# turnRacingMainInput.net
KiCad netlist of a schematic drawn in Altium Designer
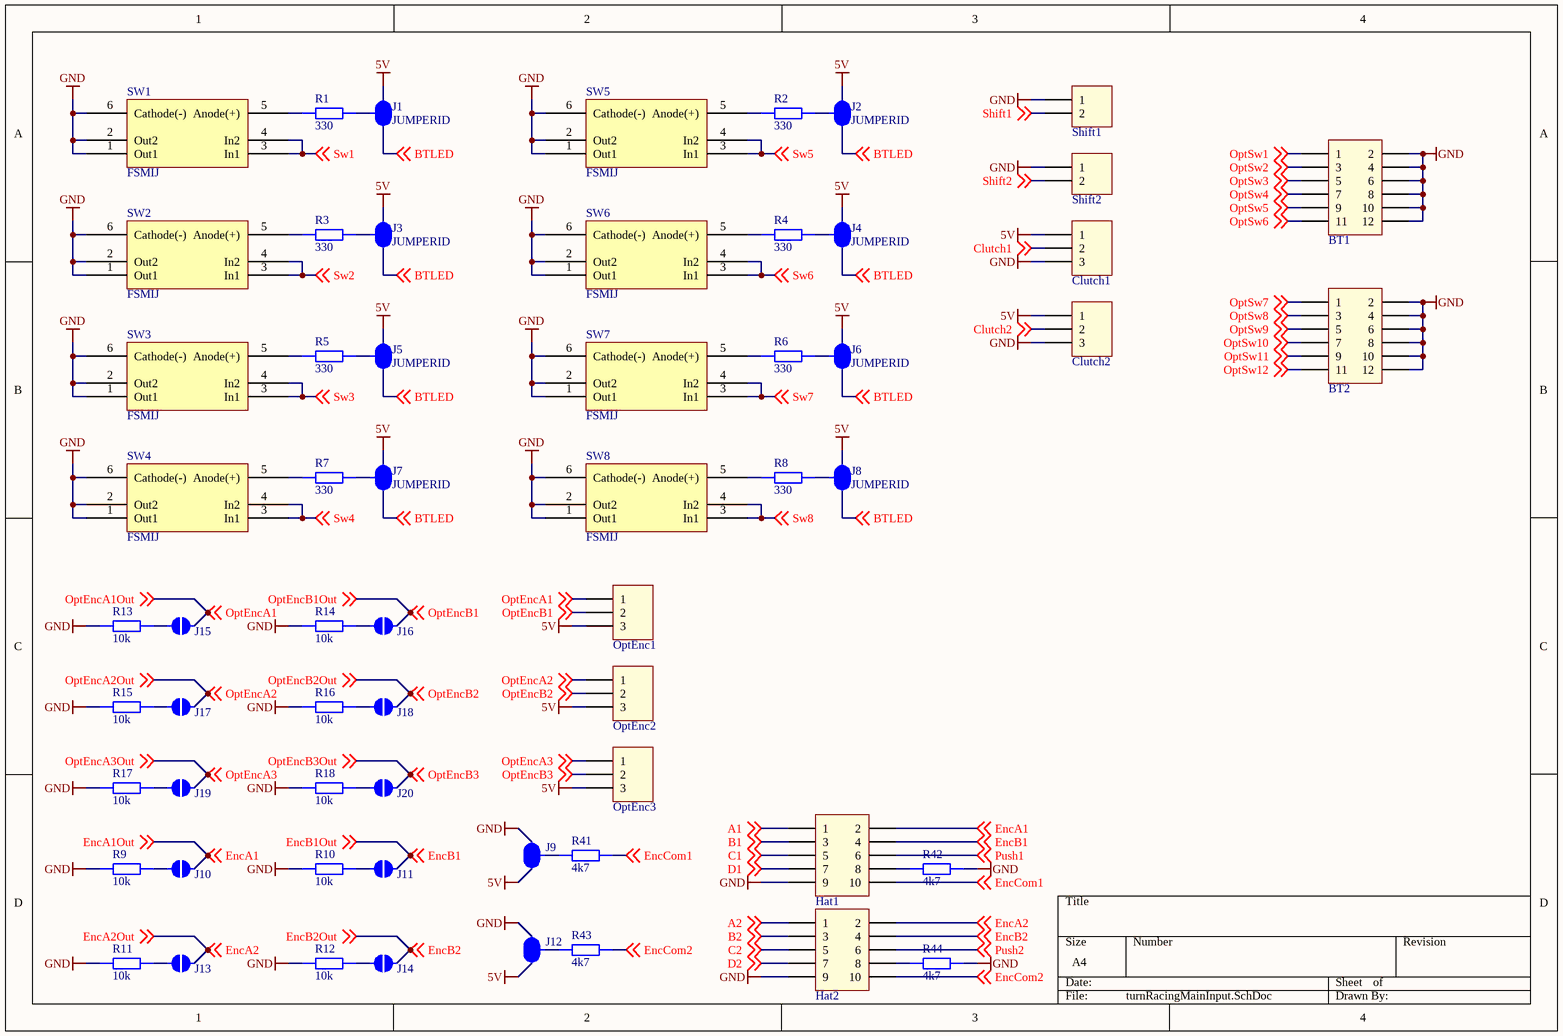
[diagram p0: turnRacingMainInput.SchDoc]

(export (version "E")
  (design (tool "Eeschema 10.0.6"))
  (components
    (comp (ref "BT1")
      (value "61301221121")
      (footprint "61301221121")
      (description "WR-PHD 2.54 mm THT Dual Pin Header, 12p")
      (fields (field (name "PUBLISHER") "Wurth Elektronik"))
      (libsource (lib "ALTIUM-PHD_2_54_THT_DUAL_PIN_HEADER_6130XX21121") (part "61301221121"))
    )
    (comp (ref "BT2")
      (value "61301221121")
      (footprint "61301221121")
      (description "WR-PHD 2.54 mm THT Dual Pin Header, 12p")
      (fields (field (name "PUBLISHER") "Wurth Elektronik"))
      (libsource (lib "ALTIUM-PHD_2_54_THT_DUAL_PIN_HEADER_6130XX21121") (part "61301221121"))
    )
    (comp (ref "Clutch1")
      (value "61300311121")
      (footprint "61300311121")
      (description "WR-PHD 2.54 mm THT Pin Header, 3p")
      (fields (field (name "PUBLISHER") "Wurth Elektronik"))
      (libsource (lib "ALTIUM-PHD_2_54_THT_DUAL_PIN_HEADER_6130XX21121") (part "61300311121"))
    )
    (comp (ref "Clutch2")
      (value "61300311121")
      (footprint "61300311121")
      (description "WR-PHD 2.54 mm THT Pin Header, 3p")
      (fields (field (name "PUBLISHER") "Wurth Elektronik"))
      (libsource (lib "ALTIUM-PHD_2_54_THT_DUAL_PIN_HEADER_6130XX21121") (part "61300311121"))
    )
    (comp (ref "Hat1")
      (value "61301021121")
      (footprint "61301021121")
      (description "WR-PHD 2.54 mm THT Dual Pin Header, 10p")
      (fields (field (name "PUBLISHER") "Wurth Elektronik"))
      (libsource (lib "ALTIUM-PHD_2_54_THT_DUAL_PIN_HEADER_6130XX21121") (part "61301021121"))
    )
    (comp (ref "Hat2")
      (value "61301021121")
      (footprint "61301021121")
      (description "WR-PHD 2.54 mm THT Dual Pin Header, 10p")
      (fields (field (name "PUBLISHER") "Wurth Elektronik"))
      (libsource (lib "ALTIUM-PHD_2_54_THT_DUAL_PIN_HEADER_6130XX21121") (part "61301021121"))
    )
    (comp (ref "J1")
      (value "JUMPERID")
      (footprint "SMD-JUMPER-3")
      (libsource (lib "Standardbauteile") (part "SMD Jumper 3"))
    )
    (comp (ref "J2")
      (value "JUMPERID")
      (footprint "SMD-JUMPER-3")
      (libsource (lib "Standardbauteile") (part "SMD Jumper 3"))
    )
    (comp (ref "J3")
      (value "JUMPERID")
      (footprint "SMD-JUMPER-3")
      (libsource (lib "Standardbauteile") (part "SMD Jumper 3"))
    )
    (comp (ref "J4")
      (value "JUMPERID")
      (footprint "SMD-JUMPER-3")
      (libsource (lib "Standardbauteile") (part "SMD Jumper 3"))
    )
    (comp (ref "J5")
      (value "JUMPERID")
      (footprint "SMD-JUMPER-3")
      (libsource (lib "Standardbauteile") (part "SMD Jumper 3"))
    )
    (comp (ref "J6")
      (value "JUMPERID")
      (footprint "SMD-JUMPER-3")
      (libsource (lib "Standardbauteile") (part "SMD Jumper 3"))
    )
    (comp (ref "J7")
      (value "JUMPERID")
      (footprint "SMD-JUMPER-3")
      (libsource (lib "Standardbauteile") (part "SMD Jumper 3"))
    )
    (comp (ref "J8")
      (value "JUMPERID")
      (footprint "SMD-JUMPER-3")
      (libsource (lib "Standardbauteile") (part "SMD Jumper 3"))
    )
    (comp (ref "J9")
      (value "JUMPERID")
      (footprint "SMD-JUMPER-3")
      (libsource (lib "") (part "SMD Jumper 3_1"))
    )
    (comp (ref "J10")
      (value "SMD Jumper open")
      (footprint "SMD-JUMPER-OPEN")
      (libsource (lib "Standardbauteile") (part "SMD Jumper open"))
    )
    (comp (ref "J11")
      (value "SMD Jumper open")
      (footprint "SMD-JUMPER-OPEN")
      (libsource (lib "Standardbauteile") (part "SMD Jumper open"))
    )
    (comp (ref "J12")
      (value "JUMPERID")
      (footprint "SMD-JUMPER-3")
      (libsource (lib "") (part "SMD Jumper 3_1"))
    )
    (comp (ref "J13")
      (value "SMD Jumper open")
      (footprint "SMD-JUMPER-OPEN")
      (libsource (lib "Standardbauteile") (part "SMD Jumper open"))
    )
    (comp (ref "J14")
      (value "SMD Jumper open")
      (footprint "SMD-JUMPER-OPEN")
      (libsource (lib "Standardbauteile") (part "SMD Jumper open"))
    )
    (comp (ref "J15")
      (value "SMD Jumper open")
      (footprint "SMD-JUMPER-OPEN")
      (libsource (lib "Standardbauteile") (part "SMD Jumper open"))
    )
    (comp (ref "J16")
      (value "SMD Jumper open")
      (footprint "SMD-JUMPER-OPEN")
      (libsource (lib "Standardbauteile") (part "SMD Jumper open"))
    )
    (comp (ref "J17")
      (value "SMD Jumper open")
      (footprint "SMD-JUMPER-OPEN")
      (libsource (lib "Standardbauteile") (part "SMD Jumper open"))
    )
    (comp (ref "J18")
      (value "SMD Jumper open")
      (footprint "SMD-JUMPER-OPEN")
      (libsource (lib "Standardbauteile") (part "SMD Jumper open"))
    )
    (comp (ref "J19")
      (value "SMD Jumper open")
      (footprint "SMD-JUMPER-OPEN")
      (libsource (lib "Standardbauteile") (part "SMD Jumper open"))
    )
    (comp (ref "J20")
      (value "SMD Jumper open")
      (footprint "SMD-JUMPER-OPEN")
      (libsource (lib "Standardbauteile") (part "SMD Jumper open"))
    )
    (comp (ref "OptEnc1")
      (value "61300311121")
      (footprint "61300311121")
      (description "WR-PHD 2.54 mm THT Pin Header, 3p")
      (fields (field (name "PUBLISHER") "Wurth Elektronik"))
      (libsource (lib "ALTIUM-PHD_2_54_THT_DUAL_PIN_HEADER_6130XX21121") (part "61300311121"))
    )
    (comp (ref "OptEnc2")
      (value "61300311121")
      (footprint "61300311121")
      (description "WR-PHD 2.54 mm THT Pin Header, 3p")
      (fields (field (name "PUBLISHER") "Wurth Elektronik"))
      (libsource (lib "ALTIUM-PHD_2_54_THT_DUAL_PIN_HEADER_6130XX21121") (part "61300311121"))
    )
    (comp (ref "OptEnc3")
      (value "61300311121")
      (footprint "61300311121")
      (description "WR-PHD 2.54 mm THT Pin Header, 3p")
      (fields (field (name "PUBLISHER") "Wurth Elektronik"))
      (libsource (lib "ALTIUM-PHD_2_54_THT_DUAL_PIN_HEADER_6130XX21121") (part "61300311121"))
    )
    (comp (ref "R1")
      (value "330")
      (footprint "STACKPOLE CSR0603")
      (description "Resistor with multiple footprints")
      (fields (field (name "Comment") "SMD Resistor"))
      (libsource (lib "") (part "SMD Resistor_1"))
    )
    (comp (ref "R2")
      (value "330")
      (footprint "STACKPOLE CSR0603")
      (description "Resistor with multiple footprints")
      (fields (field (name "Comment") "SMD Resistor"))
      (libsource (lib "") (part "SMD Resistor_1"))
    )
    (comp (ref "R3")
      (value "330")
      (footprint "STACKPOLE CSR0603")
      (description "Resistor with multiple footprints")
      (fields (field (name "Comment") "SMD Resistor"))
      (libsource (lib "") (part "SMD Resistor_1"))
    )
    (comp (ref "R4")
      (value "330")
      (footprint "STACKPOLE CSR0603")
      (description "Resistor with multiple footprints")
      (fields (field (name "Comment") "SMD Resistor"))
      (libsource (lib "") (part "SMD Resistor_1"))
    )
    (comp (ref "R5")
      (value "330")
      (footprint "STACKPOLE CSR0603")
      (description "Resistor with multiple footprints")
      (fields (field (name "Comment") "SMD Resistor"))
      (libsource (lib "") (part "SMD Resistor_1"))
    )
    (comp (ref "R6")
      (value "330")
      (footprint "STACKPOLE CSR0603")
      (description "Resistor with multiple footprints")
      (fields (field (name "Comment") "SMD Resistor"))
      (libsource (lib "") (part "SMD Resistor_1"))
    )
    (comp (ref "R7")
      (value "330")
      (footprint "STACKPOLE CSR0603")
      (description "Resistor with multiple footprints")
      (fields (field (name "Comment") "SMD Resistor"))
      (libsource (lib "") (part "SMD Resistor_1"))
    )
    (comp (ref "R8")
      (value "330")
      (footprint "STACKPOLE CSR0603")
      (description "Resistor with multiple footprints")
      (fields (field (name "Comment") "SMD Resistor"))
      (libsource (lib "") (part "SMD Resistor_1"))
    )
    (comp (ref "R9")
      (value "10k")
      (footprint "STACKPOLE CSR0603")
      (description "Resistor with multiple footprints")
      (fields (field (name "Comment") "SMD Resistor"))
      (libsource (lib "") (part "SMD Resistor_1"))
    )
    (comp (ref "R10")
      (value "10k")
      (footprint "STACKPOLE CSR0603")
      (description "Resistor with multiple footprints")
      (fields (field (name "Comment") "SMD Resistor"))
      (libsource (lib "") (part "SMD Resistor_1"))
    )
    (comp (ref "R11")
      (value "10k")
      (footprint "STACKPOLE CSR0603")
      (description "Resistor with multiple footprints")
      (fields (field (name "Comment") "SMD Resistor"))
      (libsource (lib "") (part "SMD Resistor_1"))
    )
    (comp (ref "R12")
      (value "10k")
      (footprint "STACKPOLE CSR0603")
      (description "Resistor with multiple footprints")
      (fields (field (name "Comment") "SMD Resistor"))
      (libsource (lib "") (part "SMD Resistor_1"))
    )
    (comp (ref "R13")
      (value "10k")
      (footprint "STACKPOLE CSR0603")
      (description "Resistor with multiple footprints")
      (fields (field (name "Comment") "SMD Resistor"))
      (libsource (lib "") (part "SMD Resistor_1"))
    )
    (comp (ref "R14")
      (value "10k")
      (footprint "STACKPOLE CSR0603")
      (description "Resistor with multiple footprints")
      (fields (field (name "Comment") "SMD Resistor"))
      (libsource (lib "") (part "SMD Resistor_1"))
    )
    (comp (ref "R15")
      (value "10k")
      (footprint "STACKPOLE CSR0603")
      (description "Resistor with multiple footprints")
      (fields (field (name "Comment") "SMD Resistor"))
      (libsource (lib "") (part "SMD Resistor_1"))
    )
    (comp (ref "R16")
      (value "10k")
      (footprint "STACKPOLE CSR0603")
      (description "Resistor with multiple footprints")
      (fields (field (name "Comment") "SMD Resistor"))
      (libsource (lib "") (part "SMD Resistor_1"))
    )
    (comp (ref "R17")
      (value "10k")
      (footprint "STACKPOLE CSR0603")
      (description "Resistor with multiple footprints")
      (fields (field (name "Comment") "SMD Resistor"))
      (libsource (lib "") (part "SMD Resistor_1"))
    )
    (comp (ref "R18")
      (value "10k")
      (footprint "STACKPOLE CSR0603")
      (description "Resistor with multiple footprints")
      (fields (field (name "Comment") "SMD Resistor"))
      (libsource (lib "") (part "SMD Resistor_1"))
    )
    (comp (ref "R41")
      (value "4k7")
      (footprint "STACKPOLE CSR0603")
      (description "Resistor with multiple footprints")
      (fields (field (name "Comment") "SMD Resistor"))
      (libsource (lib "Standardbauteile") (part "SMD Resistor"))
    )
    (comp (ref "R42")
      (value "4k7")
      (footprint "STACKPOLE CSR0603")
      (description "Resistor with multiple footprints")
      (fields (field (name "Comment") "SMD Resistor"))
      (libsource (lib "Standardbauteile") (part "SMD Resistor"))
    )
    (comp (ref "R43")
      (value "4k7")
      (footprint "STACKPOLE CSR0603")
      (description "Resistor with multiple footprints")
      (fields (field (name "Comment") "SMD Resistor"))
      (libsource (lib "Standardbauteile") (part "SMD Resistor"))
    )
    (comp (ref "R44")
      (value "4k7")
      (footprint "STACKPOLE CSR0603")
      (description "Resistor with multiple footprints")
      (fields (field (name "Comment") "SMD Resistor"))
      (libsource (lib "Standardbauteile") (part "SMD Resistor"))
    )
    (comp (ref "Shift1")
      (value "61300211121")
      (footprint "61300211121")
      (description "WR-PHD 2.54 mm THT Pin Header, 2p")
      (fields (field (name "PUBLISHER") "Wurth Elektronik"))
      (libsource (lib "ALTIUM-PHD_2_54_THT_DUAL_PIN_HEADER_6130XX21121") (part "61300211121"))
    )
    (comp (ref "Shift2")
      (value "61300211121")
      (footprint "61300211121")
      (description "WR-PHD 2.54 mm THT Pin Header, 2p")
      (fields (field (name "PUBLISHER") "Wurth Elektronik"))
      (libsource (lib "ALTIUM-PHD_2_54_THT_DUAL_PIN_HEADER_6130XX21121") (part "61300211121"))
    )
    (comp (ref "SW1") (value "FSMIJ") (footprint "FSMIJ") (libsource (lib "Eric") (part "FSMIJ")))
    (comp (ref "SW2") (value "FSMIJ") (footprint "FSMIJ") (libsource (lib "Eric") (part "FSMIJ")))
    (comp (ref "SW3") (value "FSMIJ") (footprint "FSMIJ") (libsource (lib "Eric") (part "FSMIJ")))
    (comp (ref "SW4") (value "FSMIJ") (footprint "FSMIJ") (libsource (lib "Eric") (part "FSMIJ")))
    (comp (ref "SW5") (value "FSMIJ") (footprint "FSMIJ") (libsource (lib "Eric") (part "FSMIJ")))
    (comp (ref "SW6") (value "FSMIJ") (footprint "FSMIJ") (libsource (lib "Eric") (part "FSMIJ")))
    (comp (ref "SW7") (value "FSMIJ") (footprint "FSMIJ") (libsource (lib "Eric") (part "FSMIJ")))
    (comp (ref "SW8") (value "FSMIJ") (footprint "FSMIJ") (libsource (lib "Eric") (part "FSMIJ")))
  )
  (nets
    (net (code "1") (name "5V") (class "Default")
      (node (ref "Clutch1") (pin "1") (pinfunction "1_1") (pintype "passive"))
      (node (ref "Clutch2") (pin "1") (pinfunction "1_1") (pintype "passive"))
      (node (ref "J1") (pin "3") (pinfunction "3_3") (pintype "passive"))
      (node (ref "J12") (pin "3") (pinfunction "3_3") (pintype "passive"))
      (node (ref "J2") (pin "3") (pinfunction "3_3") (pintype "passive"))
      (node (ref "J3") (pin "3") (pinfunction "3_3") (pintype "passive"))
      (node (ref "J4") (pin "3") (pinfunction "3_3") (pintype "passive"))
      (node (ref "J5") (pin "3") (pinfunction "3_3") (pintype "passive"))
      (node (ref "J6") (pin "3") (pinfunction "3_3") (pintype "passive"))
      (node (ref "J7") (pin "3") (pinfunction "3_3") (pintype "passive"))
      (node (ref "J8") (pin "3") (pinfunction "3_3") (pintype "passive"))
      (node (ref "J9") (pin "3") (pinfunction "3_3") (pintype "passive"))
      (node (ref "OptEnc1") (pin "3") (pinfunction "3_3") (pintype "passive"))
      (node (ref "OptEnc2") (pin "3") (pinfunction "3_3") (pintype "passive"))
      (node (ref "OptEnc3") (pin "3") (pinfunction "3_3") (pintype "passive"))
    )
    (net (code "2") (name "A1") (class "Default")
      (node (ref "Hat1") (pin "1") (pinfunction "1_1") (pintype "passive"))
    )
    (net (code "3") (name "A2") (class "Default")
      (node (ref "Hat2") (pin "1") (pinfunction "1_1") (pintype "passive"))
    )
    (net (code "4") (name "B1") (class "Default")
      (node (ref "Hat1") (pin "3") (pinfunction "3_3") (pintype "passive"))
    )
    (net (code "5") (name "B2") (class "Default")
      (node (ref "Hat2") (pin "3") (pinfunction "3_3") (pintype "passive"))
    )
    (net (code "6") (name "BTLED") (class "Default")
      (node (ref "J1") (pin "1") (pinfunction "1_1") (pintype "passive"))
      (node (ref "J2") (pin "1") (pinfunction "1_1") (pintype "passive"))
      (node (ref "J3") (pin "1") (pinfunction "1_1") (pintype "passive"))
      (node (ref "J4") (pin "1") (pinfunction "1_1") (pintype "passive"))
      (node (ref "J5") (pin "1") (pinfunction "1_1") (pintype "passive"))
      (node (ref "J6") (pin "1") (pinfunction "1_1") (pintype "passive"))
      (node (ref "J7") (pin "1") (pinfunction "1_1") (pintype "passive"))
      (node (ref "J8") (pin "1") (pinfunction "1_1") (pintype "passive"))
    )
    (net (code "7") (name "C1") (class "Default")
      (node (ref "Hat1") (pin "5") (pinfunction "5_5") (pintype "passive"))
    )
    (net (code "8") (name "C2") (class "Default")
      (node (ref "Hat2") (pin "5") (pinfunction "5_5") (pintype "passive"))
    )
    (net (code "9") (name "Clutch1") (class "Default")
      (node (ref "Clutch1") (pin "2") (pinfunction "2_2") (pintype "passive"))
    )
    (net (code "10") (name "Clutch2") (class "Default")
      (node (ref "Clutch2") (pin "2") (pinfunction "2_2") (pintype "passive"))
    )
    (net (code "11") (name "D1") (class "Default")
      (node (ref "Hat1") (pin "7") (pinfunction "7_7") (pintype "passive"))
    )
    (net (code "12") (name "D2") (class "Default")
      (node (ref "Hat2") (pin "7") (pinfunction "7_7") (pintype "passive"))
    )
    (net (code "13") (name "EncA1") (class "Default")
      (node (ref "Hat1") (pin "2") (pinfunction "2_2") (pintype "passive"))
      (node (ref "J10") (pin "1") (pinfunction "1_1") (pintype "passive"))
    )
    (net (code "14") (name "EncA2") (class "Default")
      (node (ref "Hat2") (pin "2") (pinfunction "2_2") (pintype "passive"))
      (node (ref "J13") (pin "1") (pinfunction "1_1") (pintype "passive"))
    )
    (net (code "15") (name "EncB1") (class "Default")
      (node (ref "Hat1") (pin "4") (pinfunction "4_4") (pintype "passive"))
      (node (ref "J11") (pin "1") (pinfunction "1_1") (pintype "passive"))
    )
    (net (code "16") (name "EncB2") (class "Default")
      (node (ref "Hat2") (pin "4") (pinfunction "4_4") (pintype "passive"))
      (node (ref "J14") (pin "1") (pinfunction "1_1") (pintype "passive"))
    )
    (net (code "17") (name "EncCom1") (class "Default")
      (node (ref "Hat1") (pin "10") (pinfunction "10_10") (pintype "passive"))
      (node (ref "R41") (pin "1") (pinfunction "1_1") (pintype "passive"))
    )
    (net (code "18") (name "EncCom2") (class "Default")
      (node (ref "Hat2") (pin "10") (pinfunction "10_10") (pintype "passive"))
      (node (ref "R43") (pin "1") (pinfunction "1_1") (pintype "passive"))
    )
    (net (code "19") (name "GND") (class "Default")
      (node (ref "BT1") (pin "10") (pinfunction "10_10") (pintype "passive"))
      (node (ref "BT1") (pin "12") (pinfunction "12_12") (pintype "passive"))
      (node (ref "BT1") (pin "2") (pinfunction "2_2") (pintype "passive"))
      (node (ref "BT1") (pin "4") (pinfunction "4_4") (pintype "passive"))
      (node (ref "BT1") (pin "6") (pinfunction "6_6") (pintype "passive"))
      (node (ref "BT1") (pin "8") (pinfunction "8_8") (pintype "passive"))
      (node (ref "BT2") (pin "10") (pinfunction "10_10") (pintype "passive"))
      (node (ref "BT2") (pin "12") (pinfunction "12_12") (pintype "passive"))
      (node (ref "BT2") (pin "2") (pinfunction "2_2") (pintype "passive"))
      (node (ref "BT2") (pin "4") (pinfunction "4_4") (pintype "passive"))
      (node (ref "BT2") (pin "6") (pinfunction "6_6") (pintype "passive"))
      (node (ref "BT2") (pin "8") (pinfunction "8_8") (pintype "passive"))
      (node (ref "Clutch1") (pin "3") (pinfunction "3_3") (pintype "passive"))
      (node (ref "Clutch2") (pin "3") (pinfunction "3_3") (pintype "passive"))
      (node (ref "Hat1") (pin "9") (pinfunction "9_9") (pintype "passive"))
      (node (ref "Hat2") (pin "9") (pinfunction "9_9") (pintype "passive"))
      (node (ref "J12") (pin "1") (pinfunction "1_1") (pintype "passive"))
      (node (ref "J9") (pin "1") (pinfunction "1_1") (pintype "passive"))
      (node (ref "R10") (pin "2") (pinfunction "2_2") (pintype "passive"))
      (node (ref "R11") (pin "2") (pinfunction "2_2") (pintype "passive"))
      (node (ref "R12") (pin "2") (pinfunction "2_2") (pintype "passive"))
      (node (ref "R13") (pin "2") (pinfunction "2_2") (pintype "passive"))
      (node (ref "R14") (pin "2") (pinfunction "2_2") (pintype "passive"))
      (node (ref "R15") (pin "2") (pinfunction "2_2") (pintype "passive"))
      (node (ref "R16") (pin "2") (pinfunction "2_2") (pintype "passive"))
      (node (ref "R17") (pin "2") (pinfunction "2_2") (pintype "passive"))
      (node (ref "R18") (pin "2") (pinfunction "2_2") (pintype "passive"))
      (node (ref "R42") (pin "1") (pinfunction "1_1") (pintype "passive"))
      (node (ref "R44") (pin "1") (pinfunction "1_1") (pintype "passive"))
      (node (ref "R9") (pin "2") (pinfunction "2_2") (pintype "passive"))
      (node (ref "SW1") (pin "1") (pinfunction "Out1_1") (pintype "passive"))
      (node (ref "SW1") (pin "2") (pinfunction "Out2_2") (pintype "passive"))
      (node (ref "SW1") (pin "6") (pinfunction "Cathode(-)_6") (pintype "passive"))
      (node (ref "SW2") (pin "1") (pinfunction "Out1_1") (pintype "passive"))
      (node (ref "SW2") (pin "2") (pinfunction "Out2_2") (pintype "passive"))
      (node (ref "SW2") (pin "6") (pinfunction "Cathode(-)_6") (pintype "passive"))
      (node (ref "SW3") (pin "1") (pinfunction "Out1_1") (pintype "passive"))
      (node (ref "SW3") (pin "2") (pinfunction "Out2_2") (pintype "passive"))
      (node (ref "SW3") (pin "6") (pinfunction "Cathode(-)_6") (pintype "passive"))
      (node (ref "SW4") (pin "1") (pinfunction "Out1_1") (pintype "passive"))
      (node (ref "SW4") (pin "2") (pinfunction "Out2_2") (pintype "passive"))
      (node (ref "SW4") (pin "6") (pinfunction "Cathode(-)_6") (pintype "passive"))
      (node (ref "SW5") (pin "1") (pinfunction "Out1_1") (pintype "passive"))
      (node (ref "SW5") (pin "2") (pinfunction "Out2_2") (pintype "passive"))
      (node (ref "SW5") (pin "6") (pinfunction "Cathode(-)_6") (pintype "passive"))
      (node (ref "SW6") (pin "1") (pinfunction "Out1_1") (pintype "passive"))
      (node (ref "SW6") (pin "2") (pinfunction "Out2_2") (pintype "passive"))
      (node (ref "SW6") (pin "6") (pinfunction "Cathode(-)_6") (pintype "passive"))
      (node (ref "SW7") (pin "1") (pinfunction "Out1_1") (pintype "passive"))
      (node (ref "SW7") (pin "2") (pinfunction "Out2_2") (pintype "passive"))
      (node (ref "SW7") (pin "6") (pinfunction "Cathode(-)_6") (pintype "passive"))
      (node (ref "SW8") (pin "1") (pinfunction "Out1_1") (pintype "passive"))
      (node (ref "SW8") (pin "2") (pinfunction "Out2_2") (pintype "passive"))
      (node (ref "SW8") (pin "6") (pinfunction "Cathode(-)_6") (pintype "passive"))
      (node (ref "Shift1") (pin "1") (pinfunction "1_1") (pintype "passive"))
      (node (ref "Shift2") (pin "1") (pinfunction "1_1") (pintype "passive"))
    )
    (net (code "20") (name "Net-(Hat1-Pad8)") (class "Default")
      (node (ref "Hat1") (pin "8") (pinfunction "8_8") (pintype "passive"))
      (node (ref "R42") (pin "2") (pinfunction "2_2") (pintype "passive"))
    )
    (net (code "21") (name "Net-(Hat2-Pad8)") (class "Default")
      (node (ref "Hat2") (pin "8") (pinfunction "8_8") (pintype "passive"))
      (node (ref "R44") (pin "2") (pinfunction "2_2") (pintype "passive"))
    )
    (net (code "22") (name "Net-(J1-Pad2)") (class "Default")
      (node (ref "J1") (pin "2") (pinfunction "2_2") (pintype "passive"))
      (node (ref "R1") (pin "1") (pinfunction "1_1") (pintype "passive"))
    )
    (net (code "23") (name "Net-(J2-Pad2)") (class "Default")
      (node (ref "J2") (pin "2") (pinfunction "2_2") (pintype "passive"))
      (node (ref "R2") (pin "1") (pinfunction "1_1") (pintype "passive"))
    )
    (net (code "24") (name "Net-(J3-Pad2)") (class "Default")
      (node (ref "J3") (pin "2") (pinfunction "2_2") (pintype "passive"))
      (node (ref "R3") (pin "1") (pinfunction "1_1") (pintype "passive"))
    )
    (net (code "25") (name "Net-(J4-Pad2)") (class "Default")
      (node (ref "J4") (pin "2") (pinfunction "2_2") (pintype "passive"))
      (node (ref "R4") (pin "1") (pinfunction "1_1") (pintype "passive"))
    )
    (net (code "26") (name "Net-(J5-Pad2)") (class "Default")
      (node (ref "J5") (pin "2") (pinfunction "2_2") (pintype "passive"))
      (node (ref "R5") (pin "1") (pinfunction "1_1") (pintype "passive"))
    )
    (net (code "27") (name "Net-(J6-Pad2)") (class "Default")
      (node (ref "J6") (pin "2") (pinfunction "2_2") (pintype "passive"))
      (node (ref "R6") (pin "1") (pinfunction "1_1") (pintype "passive"))
    )
    (net (code "28") (name "Net-(J7-Pad2)") (class "Default")
      (node (ref "J7") (pin "2") (pinfunction "2_2") (pintype "passive"))
      (node (ref "R7") (pin "1") (pinfunction "1_1") (pintype "passive"))
    )
    (net (code "29") (name "Net-(J8-Pad2)") (class "Default")
      (node (ref "J8") (pin "2") (pinfunction "2_2") (pintype "passive"))
      (node (ref "R8") (pin "1") (pinfunction "1_1") (pintype "passive"))
    )
    (net (code "30") (name "Net-(J9-Pad2)") (class "Default")
      (node (ref "J9") (pin "2") (pinfunction "2_2") (pintype "passive"))
      (node (ref "R41") (pin "2") (pinfunction "2_2") (pintype "passive"))
    )
    (net (code "31") (name "Net-(J10-Pad2)") (class "Default")
      (node (ref "J10") (pin "2") (pinfunction "2_2") (pintype "passive"))
      (node (ref "R9") (pin "1") (pinfunction "1_1") (pintype "passive"))
    )
    (net (code "32") (name "Net-(J11-Pad2)") (class "Default")
      (node (ref "J11") (pin "2") (pinfunction "2_2") (pintype "passive"))
      (node (ref "R10") (pin "1") (pinfunction "1_1") (pintype "passive"))
    )
    (net (code "33") (name "Net-(J12-Pad2)") (class "Default")
      (node (ref "J12") (pin "2") (pinfunction "2_2") (pintype "passive"))
      (node (ref "R43") (pin "2") (pinfunction "2_2") (pintype "passive"))
    )
    (net (code "34") (name "Net-(J13-Pad2)") (class "Default")
      (node (ref "J13") (pin "2") (pinfunction "2_2") (pintype "passive"))
      (node (ref "R11") (pin "1") (pinfunction "1_1") (pintype "passive"))
    )
    (net (code "35") (name "Net-(J14-Pad2)") (class "Default")
      (node (ref "J14") (pin "2") (pinfunction "2_2") (pintype "passive"))
      (node (ref "R12") (pin "1") (pinfunction "1_1") (pintype "passive"))
    )
    (net (code "36") (name "Net-(J15-Pad2)") (class "Default")
      (node (ref "J15") (pin "2") (pinfunction "2_2") (pintype "passive"))
      (node (ref "R13") (pin "1") (pinfunction "1_1") (pintype "passive"))
    )
    (net (code "37") (name "Net-(J16-Pad2)") (class "Default")
      (node (ref "J16") (pin "2") (pinfunction "2_2") (pintype "passive"))
      (node (ref "R14") (pin "1") (pinfunction "1_1") (pintype "passive"))
    )
    (net (code "38") (name "Net-(J17-Pad2)") (class "Default")
      (node (ref "J17") (pin "2") (pinfunction "2_2") (pintype "passive"))
      (node (ref "R15") (pin "1") (pinfunction "1_1") (pintype "passive"))
    )
    (net (code "39") (name "Net-(J18-Pad2)") (class "Default")
      (node (ref "J18") (pin "2") (pinfunction "2_2") (pintype "passive"))
      (node (ref "R16") (pin "1") (pinfunction "1_1") (pintype "passive"))
    )
    (net (code "40") (name "Net-(J19-Pad2)") (class "Default")
      (node (ref "J19") (pin "2") (pinfunction "2_2") (pintype "passive"))
      (node (ref "R17") (pin "1") (pinfunction "1_1") (pintype "passive"))
    )
    (net (code "41") (name "Net-(J20-Pad2)") (class "Default")
      (node (ref "J20") (pin "2") (pinfunction "2_2") (pintype "passive"))
      (node (ref "R18") (pin "1") (pinfunction "1_1") (pintype "passive"))
    )
    (net (code "42") (name "Net-(SW1-Anode(+))") (class "Default")
      (node (ref "R1") (pin "2") (pinfunction "2_2") (pintype "passive"))
      (node (ref "SW1") (pin "5") (pinfunction "Anode(+)_5") (pintype "passive"))
    )
    (net (code "43") (name "Net-(SW2-Anode(+))") (class "Default")
      (node (ref "R3") (pin "2") (pinfunction "2_2") (pintype "passive"))
      (node (ref "SW2") (pin "5") (pinfunction "Anode(+)_5") (pintype "passive"))
    )
    (net (code "44") (name "Net-(SW3-Anode(+))") (class "Default")
      (node (ref "R5") (pin "2") (pinfunction "2_2") (pintype "passive"))
      (node (ref "SW3") (pin "5") (pinfunction "Anode(+)_5") (pintype "passive"))
    )
    (net (code "45") (name "Net-(SW4-Anode(+))") (class "Default")
      (node (ref "R7") (pin "2") (pinfunction "2_2") (pintype "passive"))
      (node (ref "SW4") (pin "5") (pinfunction "Anode(+)_5") (pintype "passive"))
    )
    (net (code "46") (name "Net-(SW5-Anode(+))") (class "Default")
      (node (ref "R2") (pin "2") (pinfunction "2_2") (pintype "passive"))
      (node (ref "SW5") (pin "5") (pinfunction "Anode(+)_5") (pintype "passive"))
    )
    (net (code "47") (name "Net-(SW6-Anode(+))") (class "Default")
      (node (ref "R4") (pin "2") (pinfunction "2_2") (pintype "passive"))
      (node (ref "SW6") (pin "5") (pinfunction "Anode(+)_5") (pintype "passive"))
    )
    (net (code "48") (name "Net-(SW7-Anode(+))") (class "Default")
      (node (ref "R6") (pin "2") (pinfunction "2_2") (pintype "passive"))
      (node (ref "SW7") (pin "5") (pinfunction "Anode(+)_5") (pintype "passive"))
    )
    (net (code "49") (name "Net-(SW8-Anode(+))") (class "Default")
      (node (ref "R8") (pin "2") (pinfunction "2_2") (pintype "passive"))
      (node (ref "SW8") (pin "5") (pinfunction "Anode(+)_5") (pintype "passive"))
    )
    (net (code "50") (name "OptEncA1") (class "Default")
      (node (ref "J15") (pin "1") (pinfunction "1_1") (pintype "passive"))
      (node (ref "OptEnc1") (pin "1") (pinfunction "1_1") (pintype "passive"))
    )
    (net (code "51") (name "OptEncA2") (class "Default")
      (node (ref "J17") (pin "1") (pinfunction "1_1") (pintype "passive"))
      (node (ref "OptEnc2") (pin "1") (pinfunction "1_1") (pintype "passive"))
    )
    (net (code "52") (name "OptEncA3") (class "Default")
      (node (ref "J19") (pin "1") (pinfunction "1_1") (pintype "passive"))
      (node (ref "OptEnc3") (pin "1") (pinfunction "1_1") (pintype "passive"))
    )
    (net (code "53") (name "OptEncB1") (class "Default")
      (node (ref "J16") (pin "1") (pinfunction "1_1") (pintype "passive"))
      (node (ref "OptEnc1") (pin "2") (pinfunction "2_2") (pintype "passive"))
    )
    (net (code "54") (name "OptEncB2") (class "Default")
      (node (ref "J18") (pin "1") (pinfunction "1_1") (pintype "passive"))
      (node (ref "OptEnc2") (pin "2") (pinfunction "2_2") (pintype "passive"))
    )
    (net (code "55") (name "OptEncB3") (class "Default")
      (node (ref "J20") (pin "1") (pinfunction "1_1") (pintype "passive"))
      (node (ref "OptEnc3") (pin "2") (pinfunction "2_2") (pintype "passive"))
    )
    (net (code "56") (name "OptSw1") (class "Default")
      (node (ref "BT1") (pin "1") (pinfunction "1_1") (pintype "passive"))
    )
    (net (code "57") (name "OptSw2") (class "Default")
      (node (ref "BT1") (pin "3") (pinfunction "3_3") (pintype "passive"))
    )
    (net (code "58") (name "OptSw3") (class "Default")
      (node (ref "BT1") (pin "5") (pinfunction "5_5") (pintype "passive"))
    )
    (net (code "59") (name "OptSw4") (class "Default")
      (node (ref "BT1") (pin "7") (pinfunction "7_7") (pintype "passive"))
    )
    (net (code "60") (name "OptSw5") (class "Default")
      (node (ref "BT1") (pin "9") (pinfunction "9_9") (pintype "passive"))
    )
    (net (code "61") (name "OptSw6") (class "Default")
      (node (ref "BT1") (pin "11") (pinfunction "11_11") (pintype "passive"))
    )
    (net (code "62") (name "OptSw7") (class "Default")
      (node (ref "BT2") (pin "1") (pinfunction "1_1") (pintype "passive"))
    )
    (net (code "63") (name "OptSw8") (class "Default")
      (node (ref "BT2") (pin "3") (pinfunction "3_3") (pintype "passive"))
    )
    (net (code "64") (name "OptSw9") (class "Default")
      (node (ref "BT2") (pin "5") (pinfunction "5_5") (pintype "passive"))
    )
    (net (code "65") (name "OptSw10") (class "Default")
      (node (ref "BT2") (pin "7") (pinfunction "7_7") (pintype "passive"))
    )
    (net (code "66") (name "OptSw11") (class "Default")
      (node (ref "BT2") (pin "9") (pinfunction "9_9") (pintype "passive"))
    )
    (net (code "67") (name "OptSw12") (class "Default")
      (node (ref "BT2") (pin "11") (pinfunction "11_11") (pintype "passive"))
    )
    (net (code "68") (name "Push1") (class "Default")
      (node (ref "Hat1") (pin "6") (pinfunction "6_6") (pintype "passive"))
    )
    (net (code "69") (name "Push2") (class "Default")
      (node (ref "Hat2") (pin "6") (pinfunction "6_6") (pintype "passive"))
    )
    (net (code "70") (name "Shift1") (class "Default")
      (node (ref "Shift1") (pin "2") (pinfunction "2_2") (pintype "passive"))
    )
    (net (code "71") (name "Shift2") (class "Default")
      (node (ref "Shift2") (pin "2") (pinfunction "2_2") (pintype "passive"))
    )
    (net (code "72") (name "Sw1") (class "Default")
      (node (ref "SW1") (pin "3") (pinfunction "In1_3") (pintype "passive"))
      (node (ref "SW1") (pin "4") (pinfunction "In2_4") (pintype "passive"))
    )
    (net (code "73") (name "Sw2") (class "Default")
      (node (ref "SW2") (pin "3") (pinfunction "In1_3") (pintype "passive"))
      (node (ref "SW2") (pin "4") (pinfunction "In2_4") (pintype "passive"))
    )
    (net (code "74") (name "Sw3") (class "Default")
      (node (ref "SW3") (pin "3") (pinfunction "In1_3") (pintype "passive"))
      (node (ref "SW3") (pin "4") (pinfunction "In2_4") (pintype "passive"))
    )
    (net (code "75") (name "Sw4") (class "Default")
      (node (ref "SW4") (pin "3") (pinfunction "In1_3") (pintype "passive"))
      (node (ref "SW4") (pin "4") (pinfunction "In2_4") (pintype "passive"))
    )
    (net (code "76") (name "Sw5") (class "Default")
      (node (ref "SW5") (pin "3") (pinfunction "In1_3") (pintype "passive"))
      (node (ref "SW5") (pin "4") (pinfunction "In2_4") (pintype "passive"))
    )
    (net (code "77") (name "Sw6") (class "Default")
      (node (ref "SW6") (pin "3") (pinfunction "In1_3") (pintype "passive"))
      (node (ref "SW6") (pin "4") (pinfunction "In2_4") (pintype "passive"))
    )
    (net (code "78") (name "Sw7") (class "Default")
      (node (ref "SW7") (pin "3") (pinfunction "In1_3") (pintype "passive"))
      (node (ref "SW7") (pin "4") (pinfunction "In2_4") (pintype "passive"))
    )
    (net (code "79") (name "Sw8") (class "Default")
      (node (ref "SW8") (pin "3") (pinfunction "In1_3") (pintype "passive"))
      (node (ref "SW8") (pin "4") (pinfunction "In2_4") (pintype "passive"))
    )
  )
)
